# OXCO_DaughterCard_Main.net
KiCad netlist of a schematic drawn in Altium Designer
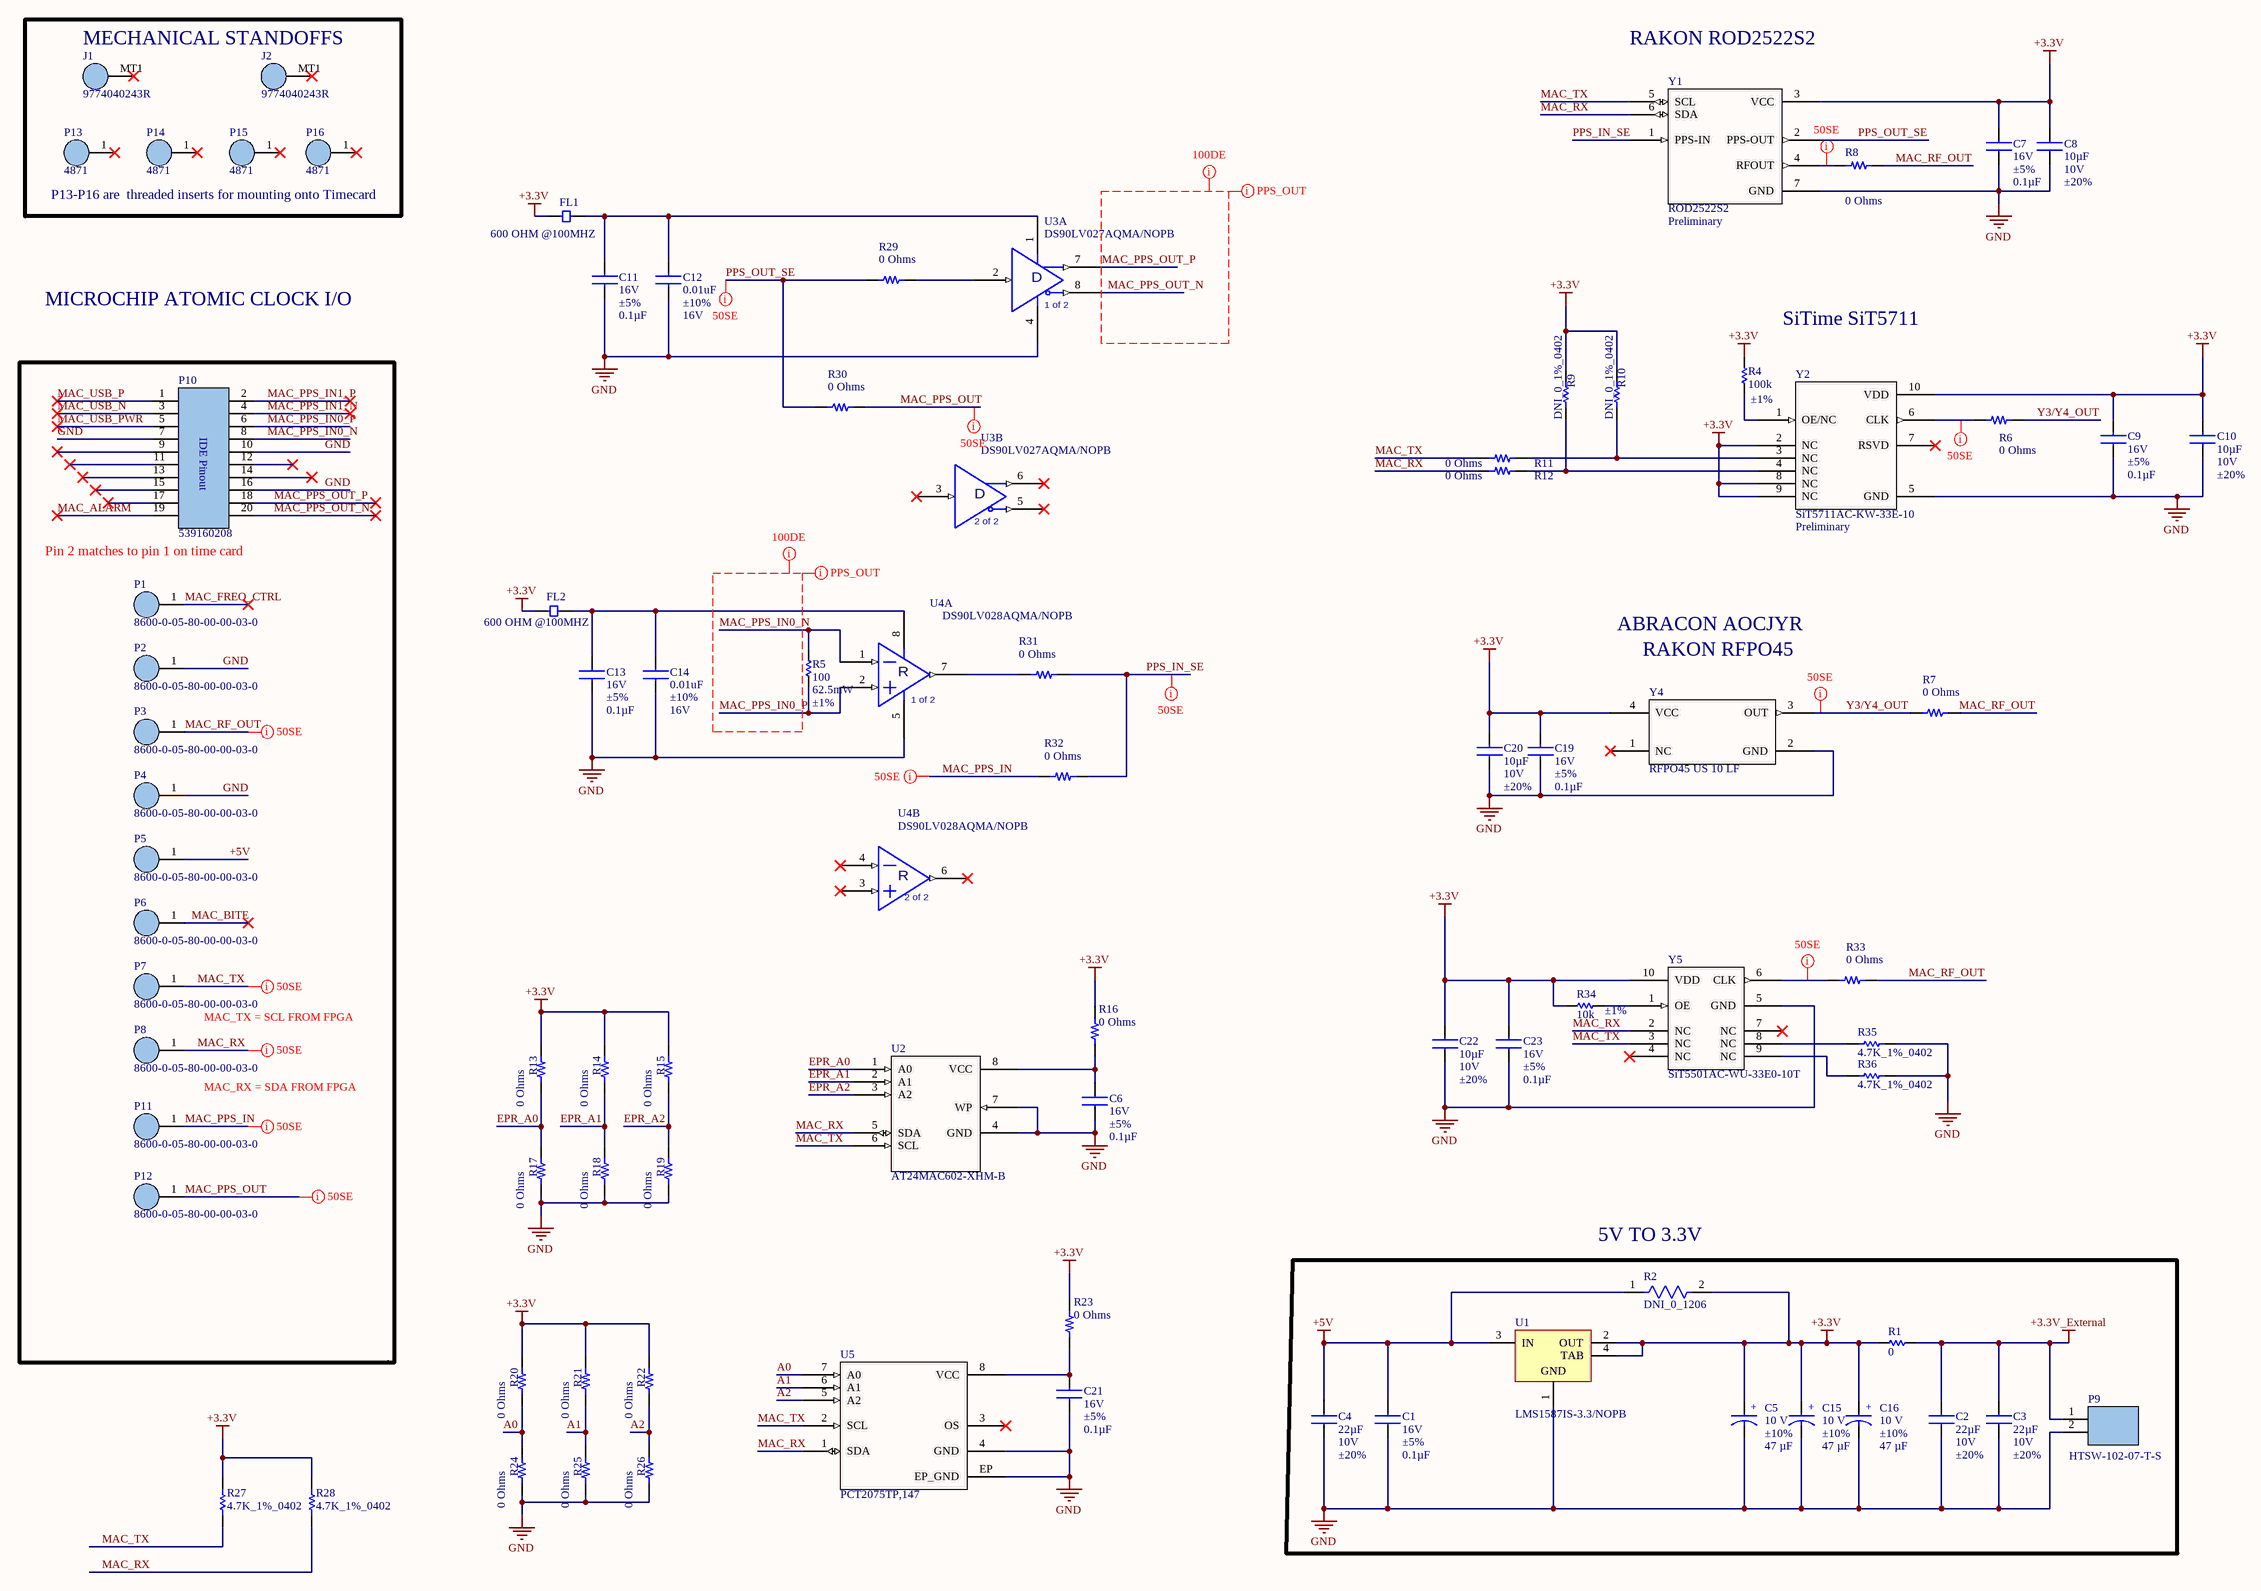
[diagram p0: OXCO_DaughterCard_Main.SchDoc]

(export (version "E")
  (design (tool "Eeschema 10.0.6"))
  (components
    (comp (ref "C1")
      (value "Samsung Electro-Mechanics_CL05B104JO5NNNC")
      (footprint "CAPC1005X055N")
      (description "CAP, CER, X7R, 0.1UF, 5%, 16V, 0402, 0.55MM T")
      (fields
        (field (name "MANUFACTURER") "Samsung Electro-Mechanics")
        (field (name "VOLTAGE RATING") "16V")
        (field (name "TOLERANCE") "±5%")
        (field (name "MANUFACTURER PART NUMBER") "CL05B104JO5NNNC")
        (field (name "CAPACITANCE") "0.1µF")
      )
      (libsource (lib "FRL Altium Server") (part "Capacitor_300mil"))
    )
    (comp (ref "C2")
      (value "Murata_GRM21BR61A226ME51L")
      (footprint "CAPC2013X140N")
      (description "CAP, CER, X5R, 22UF, 20%, 10V, 0805, 1.40MM T")
      (fields
        (field (name "CAPACITANCE") "22µF")
        (field (name "VOLTAGE RATING") "10V")
        (field (name "MANUFACTURER PART NUMBER") "GRM21BR61A226ME51L")
        (field (name "TOLERANCE") "±20%")
        (field (name "MANUFACTURER") "Murata")
      )
      (libsource (lib "FRL Altium Server") (part "Capacitor_300mil"))
    )
    (comp (ref "C3")
      (value "Murata_GRM21BR61A226ME51L")
      (footprint "CAPC2013X140N")
      (description "CAP, CER, X5R, 22UF, 20%, 10V, 0805, 1.40MM T")
      (fields
        (field (name "CAPACITANCE") "22µF")
        (field (name "VOLTAGE RATING") "10V")
        (field (name "MANUFACTURER PART NUMBER") "GRM21BR61A226ME51L")
        (field (name "TOLERANCE") "±20%")
        (field (name "MANUFACTURER") "Murata")
      )
      (libsource (lib "FRL Altium Server") (part "Capacitor_300mil"))
    )
    (comp (ref "C4")
      (value "Murata_GRM21BR61A226ME51L")
      (footprint "CAPC2013X140N")
      (description "CAP, CER, X5R, 22UF, 20%, 10V, 0805, 1.40MM T")
      (fields
        (field (name "CAPACITANCE") "22µF")
        (field (name "VOLTAGE RATING") "10V")
        (field (name "MANUFACTURER PART NUMBER") "GRM21BR61A226ME51L")
        (field (name "TOLERANCE") "±20%")
        (field (name "MANUFACTURER") "Murata")
      )
      (libsource (lib "FRL Altium Server") (part "Capacitor_300mil"))
    )
    (comp (ref "C5")
      (value "Kemet_T491B476K010AT")
      (footprint "CAPMP3528X210N_T520")
      (description "CAP TANT 47UF 10% 10V 1411")
      (fields
        (field (name "VOLTAGE RATING") "10 V")
        (field (name "MANUFACTURER PART NUMBER") "T491B476K010AT")
        (field (name "TOLERANCE") "±10%")
        (field (name "CAPACITANCE") "47 µF")
        (field (name "MANUFACTURER") "Kemet")
      )
      (libsource (lib "FRL Altium Server") (part "Capacitor_Polar_300mil"))
    )
    (comp (ref "C6")
      (value "Samsung Electro-Mechanics_CL05B104JO5NNNC")
      (footprint "CAPC1005X055N")
      (description "CAP, CER, X7R, 0.1UF, 5%, 16V, 0402, 0.55MM T")
      (fields
        (field (name "MANUFACTURER") "Samsung Electro-Mechanics")
        (field (name "VOLTAGE RATING") "16V")
        (field (name "TOLERANCE") "±5%")
        (field (name "MANUFACTURER PART NUMBER") "CL05B104JO5NNNC")
        (field (name "CAPACITANCE") "0.1µF")
      )
      (libsource (lib "FRL Altium Server") (part "Capacitor_300mil"))
    )
    (comp (ref "C7")
      (value "Samsung Electro-Mechanics_CL05B104JO5NNNC")
      (footprint "CAPC1005X055N")
      (description "CAP, CER, X7R, 0.1UF, 5%, 16V, 0402, 0.55MM T")
      (fields
        (field (name "MANUFACTURER") "Samsung Electro-Mechanics")
        (field (name "VOLTAGE RATING") "16V")
        (field (name "TOLERANCE") "±5%")
        (field (name "MANUFACTURER PART NUMBER") "CL05B104JO5NNNC")
        (field (name "CAPACITANCE") "0.1µF")
      )
      (libsource (lib "FRL Altium Server") (part "Capacitor_300mil"))
    )
    (comp (ref "C8")
      (value "Murata_GRM188D71A106MA73D")
      (footprint "CAPC1608X100N")
      (description "CAP, CER, X7T, 10UF, 20%, 10V, 0603, 1.00MM T")
      (fields
        (field (name "MANUFACTURER PART NUMBER") "GRM188D71A106MA73D")
        (field (name "CAPACITANCE") "10µF")
        (field (name "VOLTAGE RATING") "10V")
        (field (name "MANUFACTURER") "Murata")
        (field (name "TOLERANCE") "±20%")
      )
      (libsource (lib "FRL Altium Server") (part "Capacitor_300mil"))
    )
    (comp (ref "C9")
      (value "Samsung Electro-Mechanics_CL05B104JO5NNNC")
      (footprint "CAPC1005X055N")
      (description "CAP, CER, X7R, 0.1UF, 5%, 16V, 0402, 0.55MM T")
      (fields
        (field (name "MANUFACTURER") "Samsung Electro-Mechanics")
        (field (name "VOLTAGE RATING") "16V")
        (field (name "TOLERANCE") "±5%")
        (field (name "MANUFACTURER PART NUMBER") "CL05B104JO5NNNC")
        (field (name "CAPACITANCE") "0.1µF")
      )
      (libsource (lib "FRL Altium Server") (part "Capacitor_300mil"))
    )
    (comp (ref "C10")
      (value "Murata_GRM188D71A106MA73D")
      (footprint "CAPC1608X100N")
      (description "CAP, CER, X7T, 10UF, 20%, 10V, 0603, 1.00MM T")
      (fields
        (field (name "MANUFACTURER PART NUMBER") "GRM188D71A106MA73D")
        (field (name "CAPACITANCE") "10µF")
        (field (name "VOLTAGE RATING") "10V")
        (field (name "MANUFACTURER") "Murata")
        (field (name "TOLERANCE") "±20%")
      )
      (libsource (lib "FRL Altium Server") (part "Capacitor_300mil"))
    )
    (comp (ref "C11")
      (value "Samsung Electro-Mechanics_CL05B104JO5NNNC")
      (footprint "CAPC1005X055N")
      (description "CAP, CER, X7R, 0.1UF, 5%, 16V, 0402, 0.55MM T")
      (fields
        (field (name "MANUFACTURER") "Samsung Electro-Mechanics")
        (field (name "VOLTAGE RATING") "16V")
        (field (name "TOLERANCE") "±5%")
        (field (name "MANUFACTURER PART NUMBER") "CL05B104JO5NNNC")
        (field (name "CAPACITANCE") "0.1µF")
      )
      (libsource (lib "FRL Altium Server") (part "Capacitor_300mil"))
    )
    (comp (ref "C12")
      (value "Yageo_CC0402KRX7R7BB103")
      (footprint "CAPC1005X055N")
      (description "CAP, CER, X7R, 0.01UF, 10%, 16V, 0402, 0.55MM T")
      (fields
        (field (name "MANUFACTURER") "Yageo")
        (field (name "CAPACITANCE") "0.01uF")
        (field (name "TOLERANCE") "±10%")
        (field (name "MANUFACTURER PART NUMBER") "CC0402KRX7R7BB103")
        (field (name "VOLTAGE RATING") "16V")
      )
      (libsource (lib "FRL Altium Server") (part "Capacitor_300mil"))
    )
    (comp (ref "C13")
      (value "Samsung Electro-Mechanics_CL05B104JO5NNNC")
      (footprint "CAPC1005X055N")
      (description "CAP, CER, X7R, 0.1UF, 5%, 16V, 0402, 0.55MM T")
      (fields
        (field (name "MANUFACTURER") "Samsung Electro-Mechanics")
        (field (name "VOLTAGE RATING") "16V")
        (field (name "TOLERANCE") "±5%")
        (field (name "MANUFACTURER PART NUMBER") "CL05B104JO5NNNC")
        (field (name "CAPACITANCE") "0.1µF")
      )
      (libsource (lib "FRL Altium Server") (part "Capacitor_300mil"))
    )
    (comp (ref "C14")
      (value "Yageo_CC0402KRX7R7BB103")
      (footprint "CAPC1005X055N")
      (description "CAP, CER, X7R, 0.01UF, 10%, 16V, 0402, 0.55MM T")
      (fields
        (field (name "MANUFACTURER") "Yageo")
        (field (name "CAPACITANCE") "0.01uF")
        (field (name "TOLERANCE") "±10%")
        (field (name "MANUFACTURER PART NUMBER") "CC0402KRX7R7BB103")
        (field (name "VOLTAGE RATING") "16V")
      )
      (libsource (lib "FRL Altium Server") (part "Capacitor_300mil"))
    )
    (comp (ref "C15")
      (value "Kemet_T491B476K010AT")
      (footprint "CAPMP3528X210N_T520")
      (description "CAP TANT 47UF 10% 10V 1411")
      (fields
        (field (name "VOLTAGE RATING") "10 V")
        (field (name "MANUFACTURER PART NUMBER") "T491B476K010AT")
        (field (name "TOLERANCE") "±10%")
        (field (name "CAPACITANCE") "47 µF")
        (field (name "MANUFACTURER") "Kemet")
      )
      (libsource (lib "FRL Altium Server") (part "Capacitor_Polar_300mil"))
    )
    (comp (ref "C16")
      (value "Kemet_T491B476K010AT")
      (footprint "CAPMP3528X210N_T520")
      (description "CAP TANT 47UF 10% 10V 1411")
      (fields
        (field (name "VOLTAGE RATING") "10 V")
        (field (name "MANUFACTURER PART NUMBER") "T491B476K010AT")
        (field (name "TOLERANCE") "±10%")
        (field (name "CAPACITANCE") "47 µF")
        (field (name "MANUFACTURER") "Kemet")
      )
      (libsource (lib "FRL Altium Server") (part "Capacitor_Polar_300mil"))
    )
    (comp (ref "C19")
      (value "Samsung Electro-Mechanics_CL05B104JO5NNNC")
      (footprint "CAPC1005X055N")
      (description "CAP, CER, X7R, 0.1UF, 5%, 16V, 0402, 0.55MM T")
      (fields
        (field (name "MANUFACTURER") "Samsung Electro-Mechanics")
        (field (name "VOLTAGE RATING") "16V")
        (field (name "TOLERANCE") "±5%")
        (field (name "MANUFACTURER PART NUMBER") "CL05B104JO5NNNC")
        (field (name "CAPACITANCE") "0.1µF")
      )
      (libsource (lib "FRL Altium Server") (part "Capacitor_300mil"))
    )
    (comp (ref "C20")
      (value "Murata_GRM188D71A106MA73D")
      (footprint "CAPC1608X100N")
      (description "CAP, CER, X7T, 10UF, 20%, 10V, 0603, 1.00MM T")
      (fields
        (field (name "MANUFACTURER PART NUMBER") "GRM188D71A106MA73D")
        (field (name "CAPACITANCE") "10µF")
        (field (name "VOLTAGE RATING") "10V")
        (field (name "MANUFACTURER") "Murata")
        (field (name "TOLERANCE") "±20%")
      )
      (libsource (lib "FRL Altium Server") (part "Capacitor_300mil"))
    )
    (comp (ref "C21")
      (value "Samsung Electro-Mechanics_CL05B104JO5NNNC")
      (footprint "CAPC1005X055N")
      (description "CAP, CER, X7R, 0.1UF, 5%, 16V, 0402, 0.55MM T")
      (fields
        (field (name "MANUFACTURER") "Samsung Electro-Mechanics")
        (field (name "VOLTAGE RATING") "16V")
        (field (name "TOLERANCE") "±5%")
        (field (name "MANUFACTURER PART NUMBER") "CL05B104JO5NNNC")
        (field (name "CAPACITANCE") "0.1µF")
      )
      (libsource (lib "FRL Altium Server") (part "Capacitor_300mil"))
    )
    (comp (ref "C22")
      (value "Murata_GRM188R61A106ME69D")
      (footprint "CAPC1608X090N")
      (description "CAP, CER, X5R, 10UF, 20%, 10V, 0603, 0.80MM T")
      (fields
        (field (name "MANUFACTURER PART NUMBER") "GRM188R61A106ME69D")
        (field (name "CAPACITANCE") "10µF")
        (field (name "VOLTAGE RATING") "10V")
        (field (name "MANUFACTURER") "Murata")
        (field (name "TOLERANCE") "±20%")
      )
      (libsource (lib "Meta RLR Altium Enterprise Server") (part "Capacitor_300mil"))
    )
    (comp (ref "C23")
      (value "Samsung Electro-Mechanics_CL05B104JO5NNNC")
      (footprint "CAPC1005X055N")
      (description "CAP, CER, X7R, 0.1UF, 5%, 16V, 0402, 0.55MM T")
      (fields
        (field (name "MANUFACTURER") "Samsung Electro-Mechanics")
        (field (name "VOLTAGE RATING") "16V")
        (field (name "TOLERANCE") "±5%")
        (field (name "MANUFACTURER PART NUMBER") "CL05B104JO5NNNC")
        (field (name "CAPACITANCE") "0.1µF")
      )
      (libsource (lib "Meta RLR Altium Enterprise Server") (part "Capacitor_300mil"))
    )
    (comp (ref "FL1")
      (value "TDK_MPZ1608S601ATA00")
      (footprint "INDC1608X095N")
      (description "FERRITE BEAD, 600 OHM @100MHZ, 25%, 1A, 0.150 OHM DCR, 0603, 0.95MM T")
      (fields
        (field (name "MANUFACTURER PART NUMBER") "MPZ1608S601ATA00")
        (field (name "TOLERANCE") "0.25%")
        (field (name "IMPEDANCE @ FREQUENCY") "600 OHM @100MHZ")
      )
      (libsource (lib "FRL Altium Server") (part "FerriteBead_300mil"))
    )
    (comp (ref "FL2")
      (value "TDK_MPZ1608S601ATA00")
      (footprint "INDC1608X095N")
      (description "FERRITE BEAD, 600 OHM @100MHZ, 25%, 1A, 0.150 OHM DCR, 0603, 0.95MM T")
      (fields
        (field (name "MANUFACTURER PART NUMBER") "MPZ1608S601ATA00")
        (field (name "TOLERANCE") "0.25%")
        (field (name "IMPEDANCE @ FREQUENCY") "600 OHM @100MHZ")
      )
      (libsource (lib "FRL Altium Server") (part "FerriteBead_300mil"))
    )
    (comp (ref "J1")
      (value "Wurth_9774040243R")
      (footprint "TH000V_300DIAx400_001mt_9774040243R")
      (description "STANDOFF, ROUND, M2X0.4 STEEL 4MM, 9774040243R")
      (fields
        (field (name "MANUFACTURER PART NUMBER") "9774040243R")
        (field (name "MANUFACTURER") "Wurth Elektronik")
      )
      (libsource (lib "FRL Altium Server") (part "CONN_SR_000pin_001mt_RND_F"))
    )
    (comp (ref "J2")
      (value "Wurth_9774040243R")
      (footprint "TH000V_300DIAx400_001mt_9774040243R")
      (description "STANDOFF, ROUND, M2X0.4 STEEL 4MM, 9774040243R")
      (fields
        (field (name "MANUFACTURER PART NUMBER") "9774040243R")
        (field (name "MANUFACTURER") "Wurth Elektronik")
      )
      (libsource (lib "FRL Altium Server") (part "CONN_SR_000pin_001mt_RND_F"))
    )
    (comp (ref "P1")
      (value "Mill-Max_8600-0-05-80-00-00-03-0")
      (footprint "TH001V_109DIA_000mt_8600-0")
      (description "CONN, PC PIN, PRESS-FIT, 10.16MM LENGTH, TIN, TH")
      (fields
        (field (name "MANUFACTURER PART NUMBER") "8600-0-05-80-00-00-03-0")
        (field (name "MANUFACTURER") "Mill-Max Manufacturing Corp.")
      )
      (libsource (lib "FRL Altium Server") (part "CONN_SR_001pin_000mt_RND_M"))
    )
    (comp (ref "P2")
      (value "Mill-Max_8600-0-05-80-00-00-03-0")
      (footprint "TH001V_109DIA_000mt_8600-0")
      (description "CONN, PC PIN, PRESS-FIT, 10.16MM LENGTH, TIN, TH")
      (fields
        (field (name "MANUFACTURER PART NUMBER") "8600-0-05-80-00-00-03-0")
        (field (name "MANUFACTURER") "Mill-Max Manufacturing Corp.")
      )
      (libsource (lib "FRL Altium Server") (part "CONN_SR_001pin_000mt_RND_M"))
    )
    (comp (ref "P3")
      (value "Mill-Max_8600-0-05-80-00-00-03-0")
      (footprint "TH001V_109DIA_000mt_8600-0")
      (description "CONN, PC PIN, PRESS-FIT, 10.16MM LENGTH, TIN, TH")
      (fields
        (field (name "MANUFACTURER PART NUMBER") "8600-0-05-80-00-00-03-0")
        (field (name "MANUFACTURER") "Mill-Max Manufacturing Corp.")
      )
      (libsource (lib "FRL Altium Server") (part "CONN_SR_001pin_000mt_RND_M"))
    )
    (comp (ref "P4")
      (value "Mill-Max_8600-0-05-80-00-00-03-0")
      (footprint "TH001V_109DIA_000mt_8600-0")
      (description "CONN, PC PIN, PRESS-FIT, 10.16MM LENGTH, TIN, TH")
      (fields
        (field (name "MANUFACTURER PART NUMBER") "8600-0-05-80-00-00-03-0")
        (field (name "MANUFACTURER") "Mill-Max Manufacturing Corp.")
      )
      (libsource (lib "FRL Altium Server") (part "CONN_SR_001pin_000mt_RND_M"))
    )
    (comp (ref "P5")
      (value "Mill-Max_8600-0-05-80-00-00-03-0")
      (footprint "TH001V_109DIA_000mt_8600-0")
      (description "CONN, PC PIN, PRESS-FIT, 10.16MM LENGTH, TIN, TH")
      (fields
        (field (name "MANUFACTURER PART NUMBER") "8600-0-05-80-00-00-03-0")
        (field (name "MANUFACTURER") "Mill-Max Manufacturing Corp.")
      )
      (libsource (lib "FRL Altium Server") (part "CONN_SR_001pin_000mt_RND_M"))
    )
    (comp (ref "P6")
      (value "Mill-Max_8600-0-05-80-00-00-03-0")
      (footprint "TH001V_109DIA_000mt_8600-0")
      (description "CONN, PC PIN, PRESS-FIT, 10.16MM LENGTH, TIN, TH")
      (fields
        (field (name "MANUFACTURER PART NUMBER") "8600-0-05-80-00-00-03-0")
        (field (name "MANUFACTURER") "Mill-Max Manufacturing Corp.")
      )
      (libsource (lib "FRL Altium Server") (part "CONN_SR_001pin_000mt_RND_M"))
    )
    (comp (ref "P7")
      (value "Mill-Max_8600-0-05-80-00-00-03-0")
      (footprint "TH001V_109DIA_000mt_8600-0")
      (description "CONN, PC PIN, PRESS-FIT, 10.16MM LENGTH, TIN, TH")
      (fields
        (field (name "MANUFACTURER PART NUMBER") "8600-0-05-80-00-00-03-0")
        (field (name "MANUFACTURER") "Mill-Max Manufacturing Corp.")
      )
      (libsource (lib "FRL Altium Server") (part "CONN_SR_001pin_000mt_RND_M"))
    )
    (comp (ref "P8")
      (value "Mill-Max_8600-0-05-80-00-00-03-0")
      (footprint "TH001V_109DIA_000mt_8600-0")
      (description "CONN, PC PIN, PRESS-FIT, 10.16MM LENGTH, TIN, TH")
      (fields
        (field (name "MANUFACTURER PART NUMBER") "8600-0-05-80-00-00-03-0")
        (field (name "MANUFACTURER") "Mill-Max Manufacturing Corp.")
      )
      (libsource (lib "FRL Altium Server") (part "CONN_SR_001pin_000mt_RND_M"))
    )
    (comp (ref "P9")
      (value "Samtec_HTSW-102-07-T-S")
      (footprint "TH002_254_508x254x838_000mt_HTSW")
      (description "CONN, PIN, HEADER, 2POS, 2.54MM PITCH, 8.38MM H, VERT, TIN, TH")
      (fields
        (field (name "MANUFACTURER") "Samtec Inc.")
        (field (name "MANUFACTURER PART NUMBER") "HTSW-102-07-T-S")
      )
      (libsource (lib "FRL Altium Server") (part "CONN_SR_002pin_000mt_M"))
    )
    (comp (ref "P10")
      (value "Molex_539160208")
      (footprint "SM020V_50_730x310x337_000mt_53916")
      (description "CONN, B2B/FPC, HEADER, 20-POS, 0.5MM PITCH, 4.0MM H, VERT, GOLD, SMT")
      (fields (field (name "MANUFACTURER") "Molex") (field (name "MANUFACTURER PART NUMBER") "539160208"))
      (libsource (lib "FRL Altium Server") (part "CONN_DR_020pin_000mt_M"))
    )
    (comp (ref "P11")
      (value "Mill-Max_8600-0-05-80-00-00-03-0")
      (footprint "TH001V_109DIA_000mt_8600-0")
      (description "CONN, PC PIN, PRESS-FIT, 10.16MM LENGTH, TIN, TH")
      (fields
        (field (name "MANUFACTURER PART NUMBER") "8600-0-05-80-00-00-03-0")
        (field (name "MANUFACTURER") "Mill-Max Manufacturing Corp.")
      )
      (libsource (lib "FRL Altium Server") (part "CONN_SR_001pin_000mt_RND_M"))
    )
    (comp (ref "P12")
      (value "Mill-Max_8600-0-05-80-00-00-03-0")
      (footprint "TH001V_109DIA_000mt_8600-0")
      (description "CONN, PC PIN, PRESS-FIT, 10.16MM LENGTH, TIN, TH")
      (fields
        (field (name "MANUFACTURER PART NUMBER") "8600-0-05-80-00-00-03-0")
        (field (name "MANUFACTURER") "Mill-Max Manufacturing Corp.")
      )
      (libsource (lib "FRL Altium Server") (part "CONN_SR_001pin_000mt_RND_M"))
    )
    (comp (ref "P13")
      (value "4871")
      (footprint "Keystone_4871")
      (description "Round Standoff Threaded #2-56 Steel 0.063\" (1.60mm) 1/16\"")
      (fields (field (name "MANUFACTURER") "Keystone") (field (name "MANUFACTURER PART NUMBER") "4871"))
      (libsource (lib "846-01710_SCH_OCXO_DaughterCard") (part "Keystone_4871"))
    )
    (comp (ref "P14")
      (value "4871")
      (footprint "Keystone_4871")
      (description "Round Standoff Threaded #2-56 Steel 0.063\" (1.60mm) 1/16\"")
      (fields (field (name "MANUFACTURER") "Keystone") (field (name "MANUFACTURER PART NUMBER") "4871"))
      (libsource (lib "846-01710_SCH_OCXO_DaughterCard") (part "Keystone_4871"))
    )
    (comp (ref "P15")
      (value "4871")
      (footprint "Keystone_4871")
      (description "Round Standoff Threaded #2-56 Steel 0.063\" (1.60mm) 1/16\"")
      (fields (field (name "MANUFACTURER") "Keystone") (field (name "MANUFACTURER PART NUMBER") "4871"))
      (libsource (lib "846-01710_SCH_OCXO_DaughterCard") (part "Keystone_4871"))
    )
    (comp (ref "P16")
      (value "4871")
      (footprint "Keystone_4871")
      (description "Round Standoff Threaded #2-56 Steel 0.063\" (1.60mm) 1/16\"")
      (fields (field (name "MANUFACTURER") "Keystone") (field (name "MANUFACTURER PART NUMBER") "4871"))
      (libsource (lib "846-01710_SCH_OCXO_DaughterCard") (part "Keystone_4871"))
    )
    (comp (ref "R1")
      (value "Stackpole Electronics, Inc._RMCF1210ZT0R00")
      (footprint "RESC3225X070N")
      (description "RES, 0.0 OHM, 3A, 1/2W, 1210")
      (fields
        (field (name "MANUFACTURER PART NUMBER") "RMCF1210ZT0R00")
        (field (name "MANUFACTURER") "Stackpole Electronics, Inc.")
        (field (name "RESISTANCE") "0")
      )
      (libsource (lib "FRL Altium Server") (part "Resistor_300mil"))
    )
    (comp (ref "R2")
      (value "DNI_0_1206")
      (footprint "FP-RC1206-MFG")
      (description "RES SMD 0 OHM JUMPER 1/4W 1206")
      (fields
        (field (name "MANUFACTURER PART NUMBER") "RC1206JR-070RL")
        (field (name "MANUFACTURER") "YAGEO")
      )
      (libsource (lib "Altium Content Vault") (part "1029c3af85768c4190bb7ad29bc67b5"))
    )
    (comp (ref "R4")
      (value "Panasonic_ERJ-2RKF1003X")
      (footprint "RESC1005X040N")
      (description "RES, 100K OHM, 1%, 1/10W, 100PPM/C, 0402")
      (fields
        (field (name "MANUFACTURER PART NUMBER") "ERJ-2RKF1003X")
        (field (name "MANUFACTURER") "Panasonic")
        (field (name "RESISTANCE") "100k")
        (field (name "TOLERANCE") "±1%")
      )
      (libsource (lib "FRL Altium Server") (part "Resistor_300mil"))
    )
    (comp (ref "R5")
      (value "Yageo_RC0402FR-07100RL")
      (footprint "RESC1005X040N")
      (description "RES SMD 100 OHM 1% 1/16W 0402")
      (fields
        (field (name "MANUFACTURER PART NUMBER") "RC0402FR-07100RL")
        (field (name "RESISTANCE") "100")
        (field (name "POWER (WATTS)") "62.5mW")
        (field (name "MANUFACTURER") "Yageo")
        (field (name "TOLERANCE") "±1%")
      )
      (libsource (lib "FRL Altium Server") (part "Resistor_300mil"))
    )
    (comp (ref "R6")
      (value "0 Ohms")
      (footprint "YAGEO RES 0402_1005")
      (description "RES 0 OHM JUMPER 1/16W 0402")
      (fields
        (field (name "TOLERANCE") "Jumper")
        (field (name "MANUFACTURER") "Yageo")
        (field (name "RESISTANCE") "0 Ohms")
      )
      (libsource (lib "Celestial Altium Library - altium_library") (part "Resistor"))
    )
    (comp (ref "R7")
      (value "0 Ohms")
      (footprint "YAGEO RES 0402_1005")
      (description "RES 0 OHM JUMPER 1/16W 0402")
      (fields
        (field (name "TOLERANCE") "Jumper")
        (field (name "MANUFACTURER") "Yageo")
        (field (name "RESISTANCE") "0 Ohms")
      )
      (libsource (lib "Celestial Altium Library - altium_library") (part "Resistor"))
    )
    (comp (ref "R8")
      (value "0 Ohms")
      (footprint "YAGEO RES 0402_1005")
      (description "RES 0 OHM JUMPER 1/16W 0402")
      (fields
        (field (name "TOLERANCE") "Jumper")
        (field (name "MANUFACTURER") "Yageo")
        (field (name "RESISTANCE") "0 Ohms")
      )
      (libsource (lib "Celestial Altium Library - altium_library") (part "Resistor"))
    )
    (comp (ref "R9")
      (value "DNI_0_1%_0402")
      (footprint "RESC1005X40X25NL05T10")
      (fields (field (name "MANUFACTURER") "Yageo / Phycomp") (field (name "PART NUMBER") "RC0402JR-070RL"))
      (libsource (lib "Altium Content Vault") (part "RES"))
    )
    (comp (ref "R10")
      (value "DNI_0_1%_0402")
      (footprint "RESC1005X40X25NL05T10")
      (fields (field (name "MANUFACTURER") "Yageo / Phycomp") (field (name "PART NUMBER") "RC0402JR-070RL"))
      (libsource (lib "Altium Content Vault") (part "RES"))
    )
    (comp (ref "R11")
      (value "0 Ohms")
      (footprint "YAGEO RES 0402_1005")
      (description "RES 0 OHM JUMPER 1/16W 0402")
      (fields (field (name "MANUFACTURER") "Yageo") (field (name "PART NUMBER") "RC0402FR-070RL"))
      (libsource (lib "Celestial Altium Library - altium_library") (part "Resistor"))
    )
    (comp (ref "R12")
      (value "0 Ohms")
      (footprint "YAGEO RES 0402_1005")
      (description "RES 0 OHM JUMPER 1/16W 0402")
      (fields (field (name "MANUFACTURER") "Yageo") (field (name "PART NUMBER") "RC0402FR-070RL"))
      (libsource (lib "Celestial Altium Library - altium_library") (part "Resistor"))
    )
    (comp (ref "R13")
      (value "0 Ohms")
      (footprint "YAGEO RES 0402_1005")
      (description "RES 0 OHM JUMPER 1/16W 0402")
      (fields (field (name "MANUFACTURER") "Yageo") (field (name "PART NUMBER") "RC0402FR-070RL"))
      (libsource (lib "Celestial Altium Library - altium_library") (part "Resistor"))
    )
    (comp (ref "R14")
      (value "0 Ohms")
      (footprint "YAGEO RES 0402_1005")
      (description "RES 0 OHM JUMPER 1/16W 0402")
      (fields (field (name "MANUFACTURER") "Yageo") (field (name "PART NUMBER") "RC0402FR-070RL"))
      (libsource (lib "Celestial Altium Library - altium_library") (part "Resistor"))
    )
    (comp (ref "R15")
      (value "0 Ohms")
      (footprint "YAGEO RES 0402_1005")
      (description "RES 0 OHM JUMPER 1/16W 0402")
      (fields (field (name "MANUFACTURER") "Yageo") (field (name "PART NUMBER") "RC0402FR-070RL"))
      (libsource (lib "Celestial Altium Library - altium_library") (part "Resistor"))
    )
    (comp (ref "R16")
      (value "0 Ohms")
      (footprint "YAGEO RES 0402_1005")
      (description "RES 0 OHM JUMPER 1/16W 0402")
      (fields (field (name "TOLERANCE") "Jumper") (field (name "MANUFACTURER") "Yageo"))
      (libsource (lib "Celestial Altium Library - altium_library") (part "Resistor"))
    )
    (comp (ref "R17")
      (value "0 Ohms")
      (footprint "YAGEO RES 0402_1005")
      (description "RES 0 OHM JUMPER 1/16W 0402")
      (fields (field (name "MANUFACTURER") "Yageo") (field (name "PART NUMBER") "RC0402FR-070RL"))
      (libsource (lib "Celestial Altium Library - altium_library") (part "Resistor"))
    )
    (comp (ref "R18")
      (value "0 Ohms")
      (footprint "YAGEO RES 0402_1005")
      (description "RES 0 OHM JUMPER 1/16W 0402")
      (fields (field (name "MANUFACTURER") "Yageo") (field (name "PART NUMBER") "RC0402FR-070RL"))
      (libsource (lib "Celestial Altium Library - altium_library") (part "Resistor"))
    )
    (comp (ref "R19")
      (value "0 Ohms")
      (footprint "YAGEO RES 0402_1005")
      (description "RES 0 OHM JUMPER 1/16W 0402")
      (fields (field (name "MANUFACTURER") "Yageo") (field (name "PART NUMBER") "RC0402FR-070RL"))
      (libsource (lib "Celestial Altium Library - altium_library") (part "Resistor"))
    )
    (comp (ref "R20")
      (value "0 Ohms")
      (footprint "YAGEO RES 0402_1005")
      (description "RES 0 OHM JUMPER 1/16W 0402")
      (fields (field (name "MANUFACTURER") "Yageo") (field (name "PART NUMBER") "RC0402FR-070RL"))
      (libsource (lib "Celestial Altium Library - altium_library") (part "Resistor"))
    )
    (comp (ref "R21")
      (value "0 Ohms")
      (footprint "YAGEO RES 0402_1005")
      (description "RES 0 OHM JUMPER 1/16W 0402")
      (fields (field (name "MANUFACTURER") "Yageo") (field (name "PART NUMBER") "RC0402FR-070RL"))
      (libsource (lib "Celestial Altium Library - altium_library") (part "Resistor"))
    )
    (comp (ref "R22")
      (value "0 Ohms")
      (footprint "YAGEO RES 0402_1005")
      (description "RES 0 OHM JUMPER 1/16W 0402")
      (fields (field (name "MANUFACTURER") "Yageo") (field (name "PART NUMBER") "RC0402FR-070RL"))
      (libsource (lib "Celestial Altium Library - altium_library") (part "Resistor"))
    )
    (comp (ref "R23")
      (value "0 Ohms")
      (footprint "YAGEO RES 0402_1005")
      (description "RES 0 OHM JUMPER 1/16W 0402")
      (fields (field (name "TOLERANCE") "Jumper") (field (name "MANUFACTURER") "Yageo"))
      (libsource (lib "Celestial Altium Library - altium_library") (part "Resistor"))
    )
    (comp (ref "R24")
      (value "0 Ohms")
      (footprint "YAGEO RES 0402_1005")
      (description "RES 0 OHM JUMPER 1/16W 0402")
      (fields (field (name "MANUFACTURER") "Yageo") (field (name "PART NUMBER") "RC0402FR-070RL"))
      (libsource (lib "Celestial Altium Library - altium_library") (part "Resistor"))
    )
    (comp (ref "R25")
      (value "0 Ohms")
      (footprint "YAGEO RES 0402_1005")
      (description "RES 0 OHM JUMPER 1/16W 0402")
      (fields (field (name "MANUFACTURER") "Yageo") (field (name "PART NUMBER") "RC0402FR-070RL"))
      (libsource (lib "Celestial Altium Library - altium_library") (part "Resistor"))
    )
    (comp (ref "R26")
      (value "0 Ohms")
      (footprint "YAGEO RES 0402_1005")
      (description "RES 0 OHM JUMPER 1/16W 0402")
      (fields (field (name "MANUFACTURER") "Yageo") (field (name "PART NUMBER") "RC0402FR-070RL"))
      (libsource (lib "Celestial Altium Library - altium_library") (part "Resistor"))
    )
    (comp (ref "R27")
      (value "4.7K_1%_0402")
      (footprint "RESC1005X40X25LL05T05")
      (description "Chip Resistor, 4.7 KOhm, +/- 1%, 0.1 W, -55 to 155 degC, 0402 (1005 Metric), RoHS, Tape and Reel")
      (fields (field (name "TOLERANCE") "1%") (field (name "PARTNUMBER") "ERJ-2RKF4701X"))
      (libsource (lib "Altium Content Vault") (part "RES-2"))
    )
    (comp (ref "R28")
      (value "4.7K_1%_0402")
      (footprint "RESC1005X40X25LL05T05")
      (description "Chip Resistor, 4.7 KOhm, +/- 1%, 0.1 W, -55 to 155 degC, 0402 (1005 Metric), RoHS, Tape and Reel")
      (fields (field (name "TOLERANCE") "1%") (field (name "PARTNUMBER") "ERJ-2RKF4701X"))
      (libsource (lib "Altium Content Vault") (part "RES-2"))
    )
    (comp (ref "R29")
      (value "0 Ohms")
      (footprint "YAGEO RES 0402_1005")
      (description "RES 0 OHM JUMPER 1/16W 0402")
      (fields (field (name "MANUFACTURER") "Yageo") (field (name "PART NUMBER") "RC0402FR-070RL"))
      (libsource (lib "Celestial Altium Library - altium_library") (part "Resistor"))
    )
    (comp (ref "R30")
      (value "0 Ohms")
      (footprint "YAGEO RES 0402_1005")
      (description "RES 0 OHM JUMPER 1/16W 0402")
      (fields (field (name "MANUFACTURER") "Yageo") (field (name "PART NUMBER") "RC0402FR-070RL"))
      (libsource (lib "Celestial Altium Library - altium_library") (part "Resistor"))
    )
    (comp (ref "R31")
      (value "0 Ohms")
      (footprint "YAGEO RES 0402_1005")
      (description "RES 0 OHM JUMPER 1/16W 0402")
      (fields (field (name "MANUFACTURER") "Yageo") (field (name "PART NUMBER") "RC0402FR-070RL"))
      (libsource (lib "Celestial Altium Library - altium_library") (part "Resistor"))
    )
    (comp (ref "R32")
      (value "0 Ohms")
      (footprint "YAGEO RES 0402_1005")
      (description "RES 0 OHM JUMPER 1/16W 0402")
      (fields (field (name "MANUFACTURER") "Yageo") (field (name "PART NUMBER") "RC0402FR-070RL"))
      (libsource (lib "Celestial Altium Library - altium_library") (part "Resistor"))
    )
    (comp (ref "R33")
      (value "0 Ohms")
      (footprint "YAGEO RES 0402_1005")
      (description "RES 0 OHM JUMPER 1/16W 0402")
      (fields
        (field (name "TOLERANCE") "Jumper")
        (field (name "MANUFACTURER") "Yageo")
        (field (name "RESISTANCE") "0 Ohms")
      )
      (libsource (lib "Celestial Altium Library - altium_library") (part "Resistor"))
    )
    (comp (ref "R34")
      (value "Yageo_RC0201FR-0710KL")
      (footprint "RESC0603X026N")
      (description "RES, 10K OHM, 1%, 1/20W, 200PPM/C, 0201")
      (fields
        (field (name "MANUFACTURER") "Yageo")
        (field (name "MANUFACTURER PART NUMBER") "RC0201FR-0710KL")
        (field (name "RESISTANCE") "10k")
        (field (name "TOLERANCE") "±1%")
      )
      (libsource (lib "Meta RLR Altium Enterprise Server") (part "Resistor_300mil"))
    )
    (comp (ref "R35")
      (value "4.7K_1%_0402")
      (footprint "RESC1005X40X25LL05T05")
      (description "Chip Resistor, 4.7 KOhm, +/- 1%, 0.1 W, -55 to 155 degC, 0402 (1005 Metric), RoHS, Tape and Reel")
      (fields (field (name "TOLERANCE") "1%") (field (name "PARTNUMBER") "ERJ-2RKF4701X"))
      (libsource (lib "Altium Content Vault") (part "RES-2"))
    )
    (comp (ref "R36")
      (value "4.7K_1%_0402")
      (footprint "RESC1005X40X25LL05T05")
      (description "Chip Resistor, 4.7 KOhm, +/- 1%, 0.1 W, -55 to 155 degC, 0402 (1005 Metric), RoHS, Tape and Reel")
      (fields (field (name "TOLERANCE") "1%") (field (name "PARTNUMBER") "ERJ-2RKF4701X"))
      (libsource (lib "Altium Content Vault") (part "RES-2"))
    )
    (comp (ref "U1")
      (value "LMS1587IS-3.3/NOPB")
      (footprint "KTT0003B_L")
      (description "3A Low Dropout Fast Response Regulators, 3-pin TO-263, Pb-Free")
      (fields (field (name "MANUFACTURER") "Texas Instruments"))
      (libsource (lib "Altium Content Vault") (part "PM-REG-LM1086-SOT4"))
    )
    (comp (ref "U2")
      (value "Microchip_AT24MAC602-XHM-B")
      (footprint "TSSOP65P640X120-8N")
      (description "IC, EEPROM, AT24MAC602, 2K-BIT (256 X 8), 1MHZ, I2C, 1.7V - 5.5V, TSSOP-8")
      (fields
        (field (name "MANUFACTURER") "Microchip Technology")
        (field (name "MANUFACTURER PART NUMBER") "AT24MAC602-XHM-B")
      )
      (libsource (lib "FRL Altium Server") (part "IC_EEPROM_8pins_3ADD_A"))
    )
    (comp (ref "U3")
      (value "TI_DS90LV027AQMA/NOPB")
      (footprint "SOP127P600X175_8N")
      (description "IC, DRIVER, DS90LV027AQ, DUAL, DIFF, LVDS, 600MBPS, SOIC-8")
      (fields
        (field (name "MANUFACTURER PART NUMBER") "DS90LV027AQMA/NOPB")
        (field (name "MANUFACTURER") "Texas Instruments")
      )
      (libsource (lib "FRL Altium Server") (part "IC_DRVR_8P_LVDS_0R-2D"))
    )
    (comp (ref "U4")
      (value "TI_DS90LV028AQMA/NOPB")
      (footprint "SOP127P600X175_8N")
      (description "IC, RVCR, DS90LV028AQ-Q1, DUAL, DIFF, LVDS, 400MBPS, SOIC-8")
      (fields
        (field (name "MANUFACTURER PART NUMBER") "DS90LV028AQMA/NOPB")
        (field (name "MANUFACTURER") "Texas Instruments")
      )
      (libsource (lib "FRL Altium Server") (part "IC_RCVR_8P_LVDS_2R-0D"))
    )
    (comp (ref "U5")
      (value "NXP_PCT2075TP,147")
      (footprint "SON50P300X200X80-HS-9N_EP160x160_IPC")
      (description "SENSOR DIGITAL -55C-125C 8HWSON")
      (fields
        (field (name "MANUFACTURER") "NXP USA Inc.")
        (field (name "MANUFACTURER PART NUMBER") "PCT2075TP,147")
      )
      (libsource (lib "FRL Altium Server") (part "IC_SNS_8pins_1EP_PCT2075"))
    )
    (comp (ref "Y1")
      (value "Rakon_ROD2522S2")
      (footprint "OSC007_762_2540x2200x1230")
      (description "OSC, OCXO, 10MHZ - 20MHZ, 0.5PPB STAB, 3.3V, 22.0X25.4X12.3MM, SMT")
      (fields
        (field (name "MANUFACTURER PART NUMBER") "ROD2522S2")
        (field (name "PART STATUS") "Preliminary")
        (field (name "MANUFACTURER") "Rakon")
      )
      (libsource (lib "FRL Altium Server") (part "OSC_7Pins_I2C"))
    )
    (comp (ref "Y2")
      (value "SiTime_SiT5711AC-KW-33E-10")
      (footprint "SON150P700X619-10N_SiT5711")
      (description "OSC, OCXO, 10.000MHZ, 5PPM STAB, LVCMOS/CLIPPED SINE, 3.3V, DFN-10")
      (fields
        (field (name "MANUFACTURER") "SiTime")
        (field (name "MANUFACTURER PART NUMBER") "SiT5711AC-KW-33E-10")
        (field (name "PART STATUS") "Preliminary")
      )
      (libsource (lib "FRL Altium Server") (part "OSC_10Pins_OE_LVCMOS"))
    )
    (comp (ref "Y4")
      (value "Rakon_RFPO45 US 10 LF")
      (footprint "OSC004_600_970x750x430_RFP045")
      (description "OSC, OCXO, RFPO45, 10 - 26MHZ, 10PPB STAB, HCMOS, 3.3V, 9.7X7.5X4.3MM, SMT")
      (fields
        (field (name "MANUFACTURER PART NUMBER") "RFPO45 US 10 LF")
        (field (name "MANUFACTURER") "Rakon")
      )
      (libsource (lib "FRL Altium Server") (part "OSC_4Pins_001NC_001out_001gnd_001vcc_000mt"))
    )
    (comp (ref "Y5")
      (value "SiTime_SiT5501AC-WU-33E0-10T")
      (footprint "SITIME_SPL-086-CQFN-010-C07050_REV_DRAFT")
      (description "OSC, MEMS, STRATUM 3E, 10.000MHZ, 10PPB STAB, LVCMOS, 3.3V, O/P EN, 7.0X5.0X2.2MM, CQFN-10")
      (fields
        (field (name "MANUFACTURER PART NUMBER") "SiT5501AC-WU-33E0-10T")
        (field (name "MANUFACTURER") "SiTime")
      )
      (libsource (lib "Meta RLR Altium Enterprise Server") (part "SiT5501AC-WU-33E0-10T_010pin"))
    )
  )
  (nets
    (net (code "1") (name "+3.3V") (class "Default")
      (node (ref "C10") (pin "1") (pinfunction "1_1") (pintype "passive"))
      (node (ref "C15") (pin "1") (pinfunction "1_1") (pintype "passive"))
      (node (ref "C16") (pin "1") (pinfunction "1_1") (pintype "passive"))
      (node (ref "C19") (pin "1") (pinfunction "1_1") (pintype "passive"))
      (node (ref "C20") (pin "1") (pinfunction "1_1") (pintype "passive"))
      (node (ref "C22") (pin "1") (pinfunction "1_1") (pintype "passive"))
      (node (ref "C23") (pin "1") (pinfunction "1_1") (pintype "passive"))
      (node (ref "C5") (pin "1") (pinfunction "1_1") (pintype "passive"))
      (node (ref "C7") (pin "1") (pinfunction "1_1") (pintype "passive"))
      (node (ref "C8") (pin "1") (pinfunction "1_1") (pintype "passive"))
      (node (ref "C9") (pin "1") (pinfunction "1_1") (pintype "passive"))
      (node (ref "FL1") (pin "1") (pinfunction "1_1") (pintype "passive"))
      (node (ref "FL2") (pin "1") (pinfunction "1_1") (pintype "passive"))
      (node (ref "R1") (pin "1") (pinfunction "1_1") (pintype "passive"))
      (node (ref "R10") (pin "1") (pinfunction "1_1") (pintype "passive"))
      (node (ref "R13") (pin "1") (pinfunction "1_1") (pintype "passive"))
      (node (ref "R14") (pin "1") (pinfunction "1_1") (pintype "passive"))
      (node (ref "R15") (pin "1") (pinfunction "1_1") (pintype "passive"))
      (node (ref "R16") (pin "2") (pinfunction "2_2") (pintype "passive"))
      (node (ref "R2") (pin "2") (pinfunction "2_2") (pintype "passive"))
      (node (ref "R20") (pin "1") (pinfunction "1_1") (pintype "passive"))
      (node (ref "R21") (pin "1") (pinfunction "1_1") (pintype "passive"))
      (node (ref "R22") (pin "1") (pinfunction "1_1") (pintype "passive"))
      (node (ref "R23") (pin "2") (pinfunction "2_2") (pintype "passive"))
      (node (ref "R27") (pin "2") (pinfunction "2_2") (pintype "passive"))
      (node (ref "R28") (pin "2") (pinfunction "2_2") (pintype "passive"))
      (node (ref "R34") (pin "1") (pinfunction "1_1") (pintype "passive"))
      (node (ref "R4") (pin "1") (pinfunction "1_1") (pintype "passive"))
      (node (ref "R9") (pin "1") (pinfunction "1_1") (pintype "passive"))
      (node (ref "U1") (pin "2") (pinfunction "OUT_2") (pintype "power_in"))
      (node (ref "U1") (pin "4") (pinfunction "TAB_4") (pintype "power_in"))
      (node (ref "Y1") (pin "3") (pinfunction "VCC_3") (pintype "power_in"))
      (node (ref "Y2") (pin "10") (pinfunction "VDD_10") (pintype "power_in"))
      (node (ref "Y2") (pin "2") (pinfunction "NC_2") (pintype "passive"))
      (node (ref "Y2") (pin "8") (pinfunction "NC_8") (pintype "passive"))
      (node (ref "Y2") (pin "9") (pinfunction "NC_9") (pintype "passive"))
      (node (ref "Y4") (pin "4") (pinfunction "VCC_4") (pintype "power_in"))
      (node (ref "Y5") (pin "10") (pinfunction "VDD_10") (pintype "power_in"))
    )
    (net (code "2") (name "+3.3V_External") (class "Default")
      (node (ref "C2") (pin "1") (pinfunction "1_1") (pintype "passive"))
      (node (ref "C3") (pin "1") (pinfunction "1_1") (pintype "passive"))
      (node (ref "P9") (pin "1") (pinfunction "1_1") (pintype "passive"))
      (node (ref "R1") (pin "2") (pinfunction "2_2") (pintype "passive"))
    )
    (net (code "3") (name "+5V") (class "Default")
      (node (ref "C1") (pin "1") (pinfunction "1_1") (pintype "passive"))
      (node (ref "C4") (pin "1") (pinfunction "1_1") (pintype "passive"))
      (node (ref "P5") (pin "1") (pinfunction "1_1") (pintype "passive"))
      (node (ref "R2") (pin "1") (pinfunction "1_1") (pintype "passive"))
      (node (ref "U1") (pin "3") (pinfunction "IN_3") (pintype "power_in"))
    )
    (net (code "4") (name "/A0") (class "Default")
      (node (ref "R20") (pin "2") (pinfunction "2_2") (pintype "passive"))
      (node (ref "R24") (pin "1") (pinfunction "1_1") (pintype "passive"))
      (node (ref "U5") (pin "7") (pinfunction "A0_7") (pintype "input"))
    )
    (net (code "5") (name "/A1") (class "Default")
      (node (ref "R21") (pin "2") (pinfunction "2_2") (pintype "passive"))
      (node (ref "R25") (pin "1") (pinfunction "1_1") (pintype "passive"))
      (node (ref "U5") (pin "6") (pinfunction "A1_6") (pintype "input"))
    )
    (net (code "6") (name "/A2") (class "Default")
      (node (ref "R22") (pin "2") (pinfunction "2_2") (pintype "passive"))
      (node (ref "R26") (pin "1") (pinfunction "1_1") (pintype "passive"))
      (node (ref "U5") (pin "5") (pinfunction "A2_5") (pintype "input"))
    )
    (net (code "7") (name "/EPR_A0") (class "Default")
      (node (ref "R13") (pin "2") (pinfunction "2_2") (pintype "passive"))
      (node (ref "R17") (pin "1") (pinfunction "1_1") (pintype "passive"))
      (node (ref "U2") (pin "1") (pinfunction "A0_1") (pintype "input"))
    )
    (net (code "8") (name "/EPR_A1") (class "Default")
      (node (ref "R14") (pin "2") (pinfunction "2_2") (pintype "passive"))
      (node (ref "R18") (pin "1") (pinfunction "1_1") (pintype "passive"))
      (node (ref "U2") (pin "2") (pinfunction "A1_2") (pintype "input"))
    )
    (net (code "9") (name "/EPR_A2") (class "Default")
      (node (ref "R15") (pin "2") (pinfunction "2_2") (pintype "passive"))
      (node (ref "R19") (pin "1") (pinfunction "1_1") (pintype "passive"))
      (node (ref "U2") (pin "3") (pinfunction "A2_3") (pintype "input"))
    )
    (net (code "10") (name "/MAC_ALARM") (class "Default")
      (node (ref "P10") (pin "19") (pinfunction "19_19") (pintype "passive+no_connect"))
    )
    (net (code "11") (name "/MAC_BITE") (class "Default")
      (node (ref "P6") (pin "1") (pinfunction "1_1") (pintype "passive+no_connect"))
    )
    (net (code "12") (name "/MAC_FREQ_CTRL") (class "Default")
      (node (ref "P1") (pin "1") (pinfunction "1_1") (pintype "passive+no_connect"))
    )
    (net (code "13") (name "/MAC_PPS_IN") (class "Default")
      (node (ref "P11") (pin "1") (pinfunction "1_1") (pintype "passive"))
      (node (ref "R32") (pin "1") (pinfunction "1_1") (pintype "passive"))
    )
    (net (code "14") (name "/MAC_PPS_IN0_N") (class "Default")
      (node (ref "P10") (pin "8") (pinfunction "8_8") (pintype "passive"))
      (node (ref "R5") (pin "1") (pinfunction "1_1") (pintype "passive"))
      (node (ref "U4") (pin "1") (pinfunction "RIN1-_1") (pintype "input"))
    )
    (net (code "15") (name "/MAC_PPS_IN0_P") (class "Default")
      (node (ref "P10") (pin "6") (pinfunction "6_6") (pintype "passive"))
      (node (ref "R5") (pin "2") (pinfunction "2_2") (pintype "passive"))
      (node (ref "U4") (pin "2") (pinfunction "RIN1+_2") (pintype "input"))
    )
    (net (code "16") (name "/MAC_PPS_IN1_N") (class "Default")
      (node (ref "P10") (pin "4") (pinfunction "4_4") (pintype "passive+no_connect"))
    )
    (net (code "17") (name "/MAC_PPS_IN1_P") (class "Default")
      (node (ref "P10") (pin "2") (pinfunction "2_2") (pintype "passive+no_connect"))
    )
    (net (code "18") (name "/MAC_PPS_OUT") (class "Default")
      (node (ref "P12") (pin "1") (pinfunction "1_1") (pintype "passive"))
      (node (ref "R30") (pin "2") (pinfunction "2_2") (pintype "passive"))
    )
    (net (code "19") (name "/MAC_PPS_OUT_N") (class "Default")
      (node (ref "P10") (pin "20") (pinfunction "20_20") (pintype "passive"))
      (node (ref "U3") (pin "8") (pinfunction "DO-1_8") (pintype "output"))
    )
    (net (code "20") (name "/MAC_PPS_OUT_P") (class "Default")
      (node (ref "P10") (pin "18") (pinfunction "18_18") (pintype "passive"))
      (node (ref "U3") (pin "7") (pinfunction "DO+1_7") (pintype "output"))
    )
    (net (code "21") (name "/MAC_RF_OUT") (class "Default")
      (node (ref "P3") (pin "1") (pinfunction "1_1") (pintype "passive"))
      (node (ref "R33") (pin "1") (pinfunction "1_1") (pintype "passive"))
      (node (ref "R7") (pin "1") (pinfunction "1_1") (pintype "passive"))
      (node (ref "R8") (pin "1") (pinfunction "1_1") (pintype "passive"))
    )
    (net (code "22") (name "/MAC_RX") (class "Default")
      (node (ref "P8") (pin "1") (pinfunction "1_1") (pintype "passive"))
      (node (ref "R12") (pin "1") (pinfunction "1_1") (pintype "passive"))
      (node (ref "R28") (pin "1") (pinfunction "1_1") (pintype "passive"))
      (node (ref "U2") (pin "5") (pinfunction "SDA_5") (pintype "bidirectional"))
      (node (ref "U5") (pin "1") (pinfunction "SDA_1") (pintype "bidirectional"))
      (node (ref "Y1") (pin "6") (pinfunction "SDA_6") (pintype "bidirectional"))
      (node (ref "Y5") (pin "2") (pinfunction "NC_2") (pintype "passive"))
    )
    (net (code "23") (name "/MAC_TX") (class "Default")
      (node (ref "P7") (pin "1") (pinfunction "1_1") (pintype "passive"))
      (node (ref "R11") (pin "1") (pinfunction "1_1") (pintype "passive"))
      (node (ref "R27") (pin "1") (pinfunction "1_1") (pintype "passive"))
      (node (ref "U2") (pin "6") (pinfunction "SCL_6") (pintype "input"))
      (node (ref "U5") (pin "2") (pinfunction "SCL_2") (pintype "input"))
      (node (ref "Y1") (pin "5") (pinfunction "SCL_5") (pintype "bidirectional"))
      (node (ref "Y5") (pin "3") (pinfunction "NC_3") (pintype "passive"))
    )
    (net (code "24") (name "/MAC_USB_N") (class "Default")
      (node (ref "P10") (pin "3") (pinfunction "3_3") (pintype "passive+no_connect"))
    )
    (net (code "25") (name "/MAC_USB_P") (class "Default")
      (node (ref "P10") (pin "1") (pinfunction "1_1") (pintype "passive+no_connect"))
    )
    (net (code "26") (name "/MAC_USB_PWR") (class "Default")
      (node (ref "P10") (pin "5") (pinfunction "5_5") (pintype "passive+no_connect"))
    )
    (net (code "27") (name "/PPS_IN_SE") (class "Default")
      (node (ref "R31") (pin "2") (pinfunction "2_2") (pintype "passive"))
      (node (ref "R32") (pin "2") (pinfunction "2_2") (pintype "passive"))
      (node (ref "Y1") (pin "1") (pinfunction "PPS-IN_1") (pintype "input"))
    )
    (net (code "28") (name "/PPS_OUT_SE") (class "Default")
      (node (ref "R29") (pin "1") (pinfunction "1_1") (pintype "passive"))
      (node (ref "R30") (pin "1") (pinfunction "1_1") (pintype "passive"))
      (node (ref "Y1") (pin "2") (pinfunction "PPS-OUT_2") (pintype "output"))
    )
    (net (code "29") (name "/Y3{slash}Y4_OUT") (class "Default")
      (node (ref "R6") (pin "1") (pinfunction "1_1") (pintype "passive"))
      (node (ref "R7") (pin "2") (pinfunction "2_2") (pintype "passive"))
      (node (ref "Y4") (pin "3") (pinfunction "OUT_3") (pintype "output"))
    )
    (net (code "30") (name "GND") (class "Default")
      (node (ref "C1") (pin "2") (pinfunction "2_2") (pintype "passive"))
      (node (ref "C10") (pin "2") (pinfunction "2_2") (pintype "passive"))
      (node (ref "C11") (pin "2") (pinfunction "2_2") (pintype "passive"))
      (node (ref "C12") (pin "2") (pinfunction "2_2") (pintype "passive"))
      (node (ref "C13") (pin "2") (pinfunction "2_2") (pintype "passive"))
      (node (ref "C14") (pin "2") (pinfunction "2_2") (pintype "passive"))
      (node (ref "C15") (pin "2") (pinfunction "2_2") (pintype "passive"))
      (node (ref "C16") (pin "2") (pinfunction "2_2") (pintype "passive"))
      (node (ref "C19") (pin "2") (pinfunction "2_2") (pintype "passive"))
      (node (ref "C2") (pin "2") (pinfunction "2_2") (pintype "passive"))
      (node (ref "C20") (pin "2") (pinfunction "2_2") (pintype "passive"))
      (node (ref "C21") (pin "2") (pinfunction "2_2") (pintype "passive"))
      (node (ref "C22") (pin "2") (pinfunction "2_2") (pintype "passive"))
      (node (ref "C23") (pin "2") (pinfunction "2_2") (pintype "passive"))
      (node (ref "C3") (pin "2") (pinfunction "2_2") (pintype "passive"))
      (node (ref "C4") (pin "2") (pinfunction "2_2") (pintype "passive"))
      (node (ref "C5") (pin "2") (pinfunction "2_2") (pintype "passive"))
      (node (ref "C6") (pin "2") (pinfunction "2_2") (pintype "passive"))
      (node (ref "C7") (pin "2") (pinfunction "2_2") (pintype "passive"))
      (node (ref "C8") (pin "2") (pinfunction "2_2") (pintype "passive"))
      (node (ref "C9") (pin "2") (pinfunction "2_2") (pintype "passive"))
      (node (ref "P10") (pin "10") (pinfunction "10_10") (pintype "passive"))
      (node (ref "P10") (pin "16") (pinfunction "16_16") (pintype "passive"))
      (node (ref "P10") (pin "7") (pinfunction "7_7") (pintype "passive"))
      (node (ref "P2") (pin "1") (pinfunction "1_1") (pintype "passive"))
      (node (ref "P4") (pin "1") (pinfunction "1_1") (pintype "passive"))
      (node (ref "P9") (pin "2") (pinfunction "2_2") (pintype "passive"))
      (node (ref "R17") (pin "2") (pinfunction "2_2") (pintype "passive"))
      (node (ref "R18") (pin "2") (pinfunction "2_2") (pintype "passive"))
      (node (ref "R19") (pin "2") (pinfunction "2_2") (pintype "passive"))
      (node (ref "R24") (pin "2") (pinfunction "2_2") (pintype "passive"))
      (node (ref "R25") (pin "2") (pinfunction "2_2") (pintype "passive"))
      (node (ref "R26") (pin "2") (pinfunction "2_2") (pintype "passive"))
      (node (ref "R35") (pin "1") (pinfunction "1_1") (pintype "passive"))
      (node (ref "R36") (pin "1") (pinfunction "1_1") (pintype "passive"))
      (node (ref "U1") (pin "1") (pinfunction "GND_1") (pintype "power_in"))
      (node (ref "U2") (pin "4") (pinfunction "GND_4") (pintype "power_in"))
      (node (ref "U2") (pin "7") (pinfunction "WP_7") (pintype "input"))
      (node (ref "U3") (pin "4") (pinfunction "GND_4") (pintype "power_in"))
      (node (ref "U4") (pin "5") (pinfunction "GND_5") (pintype "power_in"))
      (node (ref "U5") (pin "4") (pinfunction "GND_4") (pintype "power_in"))
      (node (ref "U5") (pin "EP") (pinfunction "EP_GND_EP") (pintype "power_in"))
      (node (ref "Y1") (pin "7") (pinfunction "GND_7") (pintype "power_in"))
      (node (ref "Y2") (pin "5") (pinfunction "GND_5") (pintype "power_in"))
      (node (ref "Y4") (pin "2") (pinfunction "GND_2") (pintype "power_in"))
      (node (ref "Y5") (pin "5") (pinfunction "GND_5") (pintype "power_in"))
    )
    (net (code "31") (name "Net-(R10-Pad2)") (class "Default")
      (node (ref "R10") (pin "2") (pinfunction "2_2") (pintype "passive"))
      (node (ref "R11") (pin "2") (pinfunction "2_2") (pintype "passive"))
      (node (ref "Y2") (pin "3") (pinfunction "NC_3") (pintype "passive"))
    )
    (net (code "32") (name "Net-(R12-Pad2)") (class "Default")
      (node (ref "R12") (pin "2") (pinfunction "2_2") (pintype "passive"))
      (node (ref "R9") (pin "2") (pinfunction "2_2") (pintype "passive"))
      (node (ref "Y2") (pin "4") (pinfunction "NC_4") (pintype "passive"))
    )
    (net (code "33") (name "Net-(R35-Pad2)") (class "Default")
      (node (ref "R35") (pin "2") (pinfunction "2_2") (pintype "passive"))
      (node (ref "Y5") (pin "8") (pinfunction "NC_8") (pintype "passive"))
    )
    (net (code "34") (name "Net-(R36-Pad2)") (class "Default")
      (node (ref "R36") (pin "2") (pinfunction "2_2") (pintype "passive"))
      (node (ref "Y5") (pin "9") (pinfunction "NC_9") (pintype "passive"))
    )
    (net (code "35") (name "Net-(U2-VCC)") (class "Default")
      (node (ref "C6") (pin "1") (pinfunction "1_1") (pintype "passive"))
      (node (ref "R16") (pin "1") (pinfunction "1_1") (pintype "passive"))
      (node (ref "U2") (pin "8") (pinfunction "VCC_8") (pintype "power_in"))
    )
    (net (code "36") (name "Net-(U3A-DI1)") (class "Default")
      (node (ref "R29") (pin "2") (pinfunction "2_2") (pintype "passive"))
      (node (ref "U3") (pin "2") (pinfunction "DI1_2") (pintype "input"))
    )
    (net (code "37") (name "Net-(U3A-VCC)") (class "Default")
      (node (ref "C11") (pin "1") (pinfunction "1_1") (pintype "passive"))
      (node (ref "C12") (pin "1") (pinfunction "1_1") (pintype "passive"))
      (node (ref "FL1") (pin "2") (pinfunction "2_2") (pintype "passive"))
      (node (ref "U3") (pin "1") (pinfunction "VCC_1") (pintype "power_in"))
    )
    (net (code "38") (name "Net-(U4A-ROUT1)") (class "Default")
      (node (ref "R31") (pin "1") (pinfunction "1_1") (pintype "passive"))
      (node (ref "U4") (pin "7") (pinfunction "ROUT1_7") (pintype "output"))
    )
    (net (code "39") (name "Net-(U4A-VCC)") (class "Default")
      (node (ref "C13") (pin "1") (pinfunction "1_1") (pintype "passive"))
      (node (ref "C14") (pin "1") (pinfunction "1_1") (pintype "passive"))
      (node (ref "FL2") (pin "2") (pinfunction "2_2") (pintype "passive"))
      (node (ref "U4") (pin "8") (pinfunction "VCC_8") (pintype "power_in"))
    )
    (net (code "40") (name "Net-(U5-VCC)") (class "Default")
      (node (ref "C21") (pin "1") (pinfunction "1_1") (pintype "passive"))
      (node (ref "R23") (pin "1") (pinfunction "1_1") (pintype "passive"))
      (node (ref "U5") (pin "8") (pinfunction "VCC_8") (pintype "power_in"))
    )
    (net (code "41") (name "Net-(Y1-RFOUT)") (class "Default")
      (node (ref "R8") (pin "2") (pinfunction "2_2") (pintype "passive"))
      (node (ref "Y1") (pin "4") (pinfunction "RFOUT_4") (pintype "output"))
    )
    (net (code "42") (name "Net-(Y2-CLK)") (class "Default")
      (node (ref "R6") (pin "2") (pinfunction "2_2") (pintype "passive"))
      (node (ref "Y2") (pin "6") (pinfunction "CLK_6") (pintype "output"))
    )
    (net (code "43") (name "Net-(Y2-OE{slash}NC)") (class "Default")
      (node (ref "R4") (pin "2") (pinfunction "2_2") (pintype "passive"))
      (node (ref "Y2") (pin "1") (pinfunction "OE/NC_1") (pintype "input"))
    )
    (net (code "44") (name "Net-(Y5-CLK)") (class "Default")
      (node (ref "R33") (pin "2") (pinfunction "2_2") (pintype "passive"))
      (node (ref "Y5") (pin "6") (pinfunction "CLK_6") (pintype "output"))
    )
    (net (code "45") (name "Net-(Y5-OE)") (class "Default")
      (node (ref "R34") (pin "2") (pinfunction "2_2") (pintype "passive"))
      (node (ref "Y5") (pin "1") (pinfunction "OE_1") (pintype "input"))
    )
    (net (code "46") (name "unconnected-(J1-PadMT1)") (class "Default")
      (node (ref "J1") (pin "MT1") (pinfunction "MT1_MT1") (pintype "passive+no_connect"))
    )
    (net (code "47") (name "unconnected-(J2-PadMT1)") (class "Default")
      (node (ref "J2") (pin "MT1") (pinfunction "MT1_MT1") (pintype "passive+no_connect"))
    )
    (net (code "48") (name "unconnected-(P10-Pad9)") (class "Default")
      (node (ref "P10") (pin "9") (pinfunction "9_9") (pintype "passive+no_connect"))
    )
    (net (code "49") (name "unconnected-(P10-Pad11)") (class "Default")
      (node (ref "P10") (pin "11") (pinfunction "11_11") (pintype "passive+no_connect"))
    )
    (net (code "50") (name "unconnected-(P10-Pad12)") (class "Default")
      (node (ref "P10") (pin "12") (pinfunction "12_12") (pintype "passive+no_connect"))
    )
    (net (code "51") (name "unconnected-(P10-Pad13)") (class "Default")
      (node (ref "P10") (pin "13") (pinfunction "13_13") (pintype "passive+no_connect"))
    )
    (net (code "52") (name "unconnected-(P10-Pad14)") (class "Default")
      (node (ref "P10") (pin "14") (pinfunction "14_14") (pintype "passive+no_connect"))
    )
    (net (code "53") (name "unconnected-(P10-Pad15)") (class "Default")
      (node (ref "P10") (pin "15") (pinfunction "15_15") (pintype "passive+no_connect"))
    )
    (net (code "54") (name "unconnected-(P10-Pad17)") (class "Default")
      (node (ref "P10") (pin "17") (pinfunction "17_17") (pintype "passive+no_connect"))
    )
    (net (code "55") (name "unconnected-(P13-Pad1)") (class "Default")
      (node (ref "P13") (pin "1") (pinfunction "1_1") (pintype "passive+no_connect"))
    )
    (net (code "56") (name "unconnected-(P14-Pad1)") (class "Default")
      (node (ref "P14") (pin "1") (pinfunction "1_1") (pintype "passive+no_connect"))
    )
    (net (code "57") (name "unconnected-(P15-Pad1)") (class "Default")
      (node (ref "P15") (pin "1") (pinfunction "1_1") (pintype "passive+no_connect"))
    )
    (net (code "58") (name "unconnected-(P16-Pad1)") (class "Default")
      (node (ref "P16") (pin "1") (pinfunction "1_1") (pintype "passive+no_connect"))
    )
    (net (code "59") (name "unconnected-(U3B-DI2-Pad3)") (class "Default")
      (node (ref "U3") (pin "3") (pinfunction "DI2_3") (pintype "input+no_connect"))
    )
    (net (code "60") (name "unconnected-(U3B-DO+2-Pad6)") (class "Default")
      (node (ref "U3") (pin "6") (pinfunction "DO+2_6") (pintype "output+no_connect"))
    )
    (net (code "61") (name "unconnected-(U3B-DO-2-Pad5)") (class "Default")
      (node (ref "U3") (pin "5") (pinfunction "DO-2_5") (pintype "output+no_connect"))
    )
    (net (code "62") (name "unconnected-(U4B-RIN2+-Pad3)") (class "Default")
      (node (ref "U4") (pin "3") (pinfunction "RIN2+_3") (pintype "input+no_connect"))
    )
    (net (code "63") (name "unconnected-(U4B-RIN2--Pad4)") (class "Default")
      (node (ref "U4") (pin "4") (pinfunction "RIN2-_4") (pintype "input+no_connect"))
    )
    (net (code "64") (name "unconnected-(U4B-ROUT2-Pad6)") (class "Default")
      (node (ref "U4") (pin "6") (pinfunction "ROUT2_6") (pintype "output+no_connect"))
    )
    (net (code "65") (name "unconnected-(U5-OS-Pad3)") (class "Default")
      (node (ref "U5") (pin "3") (pinfunction "OS_3") (pintype "passive+no_connect"))
    )
    (net (code "66") (name "unconnected-(Y2-RSVD-Pad7)") (class "Default")
      (node (ref "Y2") (pin "7") (pinfunction "RSVD_7") (pintype "passive+no_connect"))
    )
    (net (code "67") (name "unconnected-(Y4-NC-Pad1)") (class "Default")
      (node (ref "Y4") (pin "1") (pinfunction "NC_1") (pintype "passive+no_connect"))
    )
    (net (code "68") (name "unconnected-(Y5-NC-Pad4)") (class "Default")
      (node (ref "Y5") (pin "4") (pinfunction "NC_4") (pintype "passive+no_connect"))
    )
    (net (code "69") (name "unconnected-(Y5-NC-Pad7)") (class "Default")
      (node (ref "Y5") (pin "7") (pinfunction "NC_7") (pintype "passive+no_connect"))
    )
  )
)
